# audio.net
KiCad netlist of a schematic drawn in Altium Designer
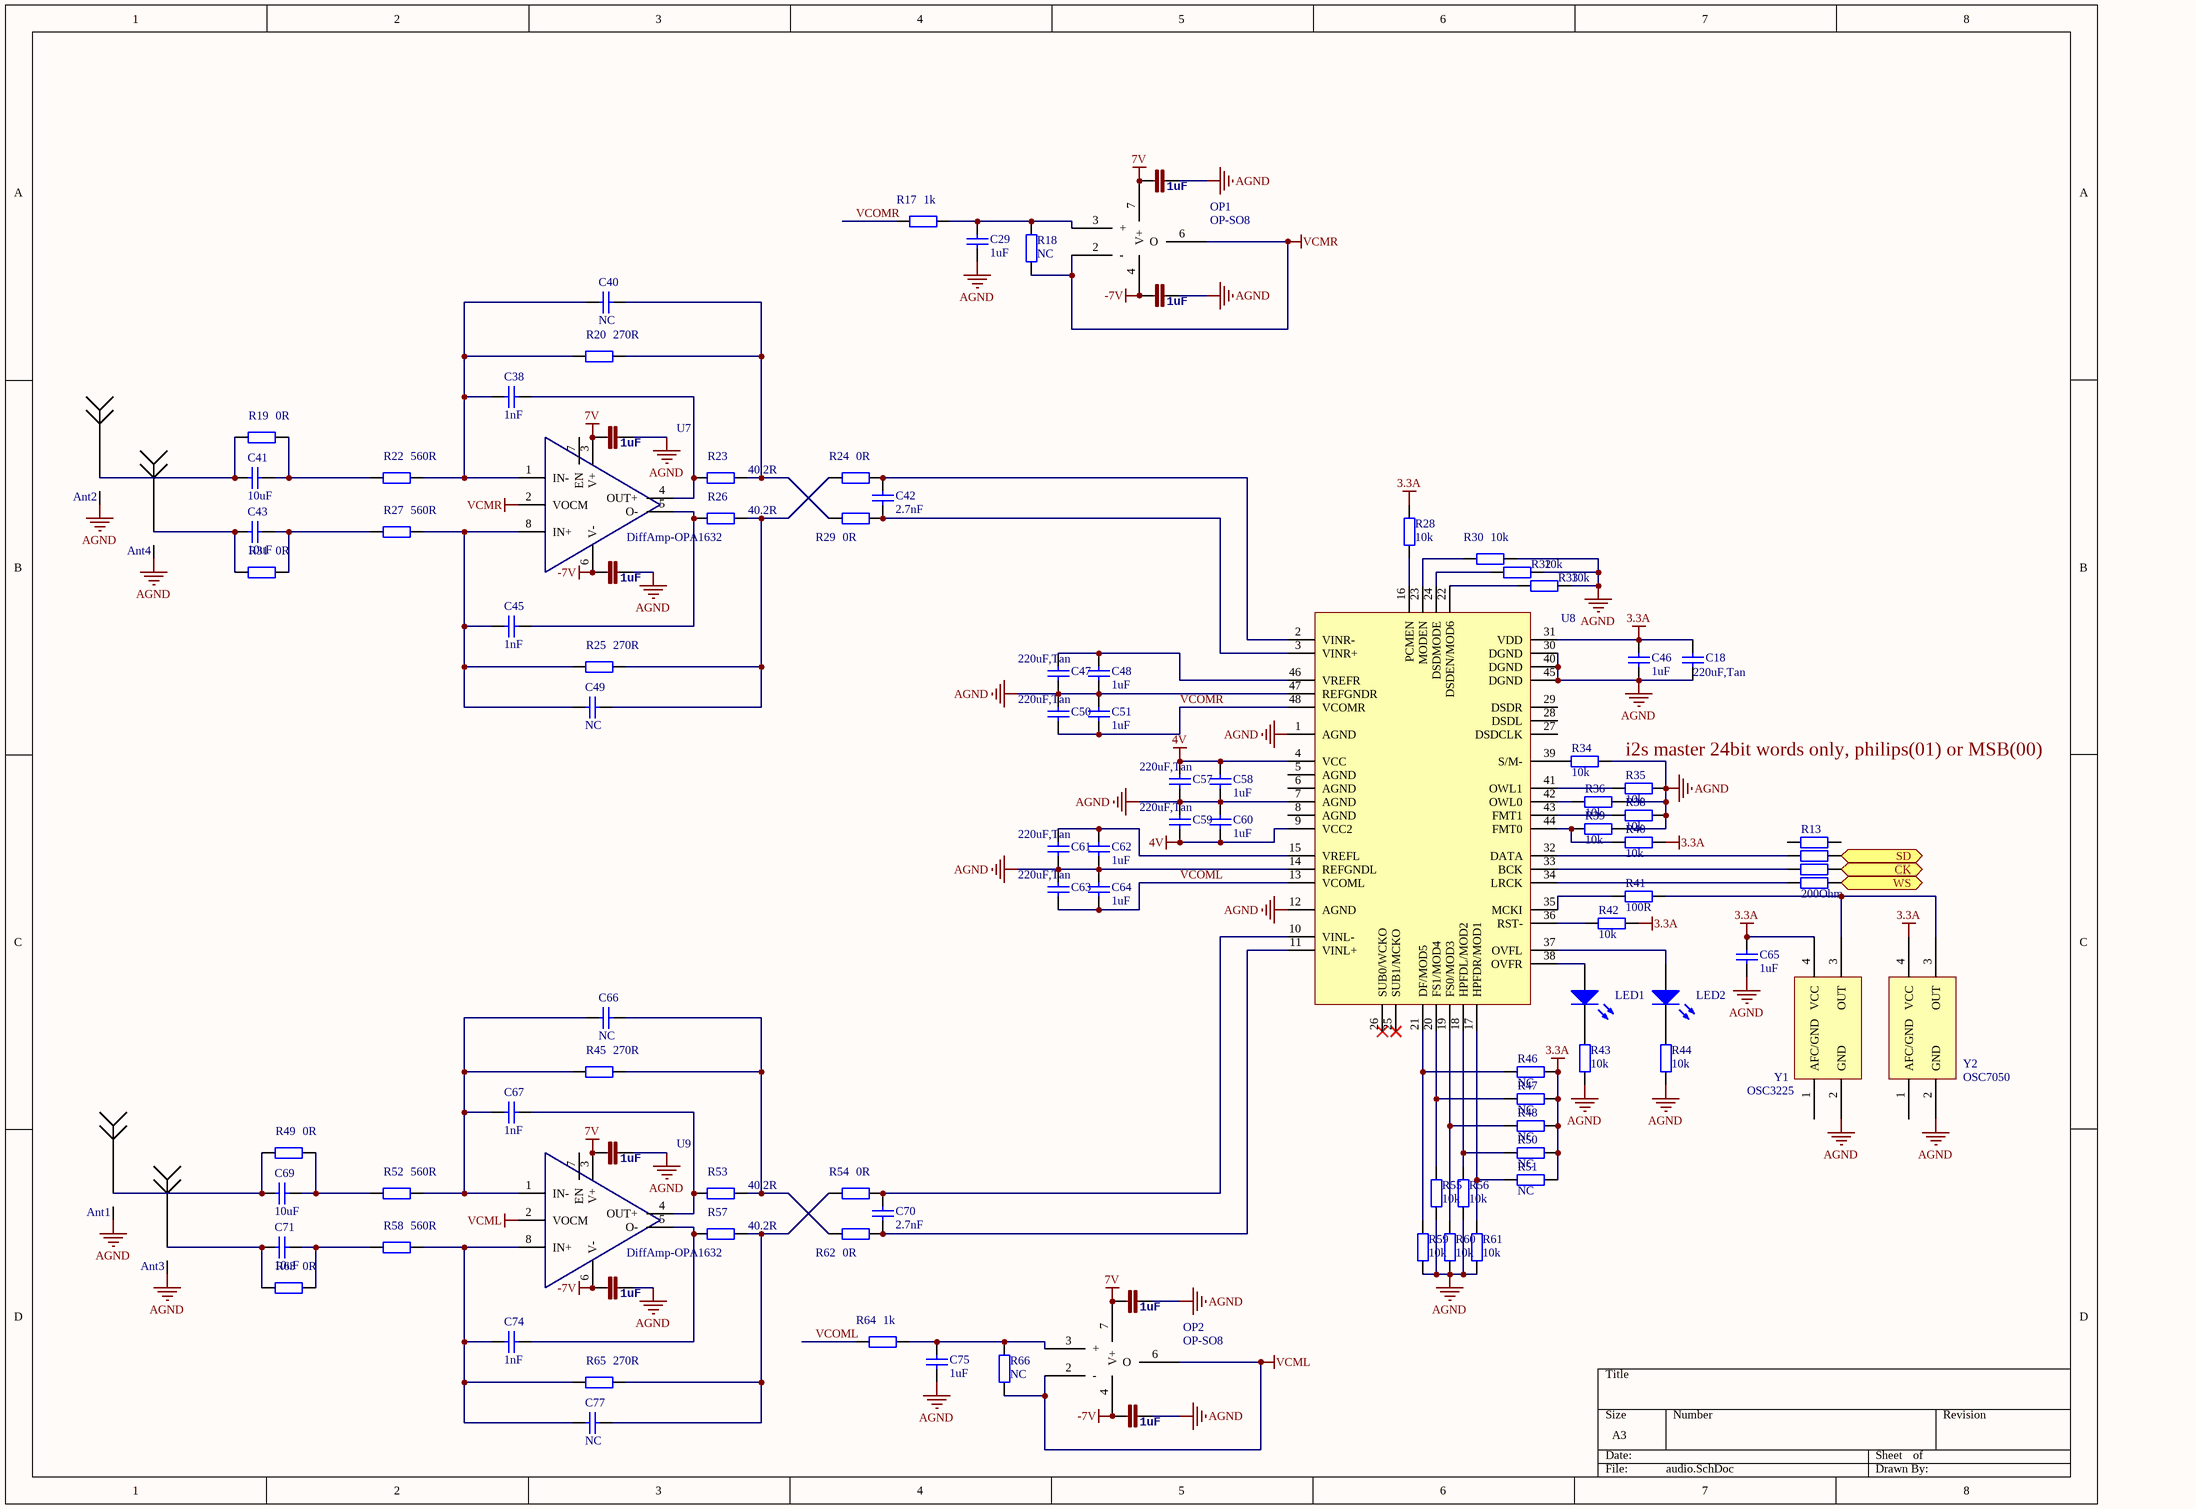
[diagram p0: audio.SchDoc]

(export (version "E")
  (design (tool "Eeschema 10.0.6"))
  (components
    (comp (ref "Ant1") (value "Antenna") (footprint "SMA-2C") (libsource (lib "F4SDR") (part "Antenna")))
    (comp (ref "Ant2")
      (value "Antenna")
      (footprint "BK5811:SMA-2C")
      (libsource (lib "F4SDR") (part "Antenna"))
    )
    (comp (ref "Ant3") (value "Antenna") (footprint "SMA-2C") (libsource (lib "F4SDR") (part "Antenna")))
    (comp (ref "Ant4") (value "Antenna") (footprint "SMA-2C") (libsource (lib "F4SDR") (part "Antenna")))
    (comp (ref "C18")
      (value "220uF,Tan")
      (footprint "1210")
      (description "Capacitor")
      (fields (field (name "PUBLISHER") "Altium Limited"))
      (libsource (lib "RTC6705") (part "Cap"))
    )
    (comp (ref "C29")
      (value "1uF")
      (footprint "0402")
      (description "Capacitor")
      (libsource (lib "RTC6705") (part "Cap"))
    )
    (comp (ref "C37")
      (value "1uF")
      (footprint "0603L")
      (description "<b>Capacitor</b>\nStandard 0603 ceramic capacitor, and 0.1\" leaded capacitor.")
      (fields (field (name "PARTNO") "CC0402ZRY5V7BB104"))
      (libsource (lib "pixhawk2") (part "CAP0402-CAP"))
    )
    (comp (ref "C38")
      (value "1nF")
      (footprint "0805")
      (description "Capacitor")
      (fields (field (name "PUBLISHER") "Altium Limited"))
      (libsource (lib "RTC6705") (part "Cap"))
    )
    (comp (ref "C39")
      (value "1uF")
      (footprint "0603L")
      (description "<b>Capacitor</b>\nStandard 0603 ceramic capacitor, and 0.1\" leaded capacitor.")
      (fields (field (name "PARTNO") "CC0402ZRY5V7BB104"))
      (libsource (lib "pixhawk2") (part "CAP0402-CAP"))
    )
    (comp (ref "C40")
      (value "NC")
      (footprint "0805")
      (description "Capacitor")
      (fields (field (name "PUBLISHER") "Altium Limited"))
      (libsource (lib "RTC6705") (part "Cap"))
    )
    (comp (ref "C41")
      (value "10uF")
      (footprint "CL21-5mm-1F")
      (description "Capacitor")
      (fields (field (name "PUBLISHER") "Altium Limited"))
      (libsource (lib "RTC6705") (part "Cap"))
    )
    (comp (ref "C42")
      (value "2.7nF")
      (footprint "0805")
      (description "Capacitor")
      (fields (field (name "PUBLISHER") "Altium Limited"))
      (libsource (lib "RTC6705") (part "Cap"))
    )
    (comp (ref "C43")
      (value "10uF")
      (footprint "CL21-5mm-1F")
      (description "Capacitor")
      (fields (field (name "PUBLISHER") "Altium Limited"))
      (libsource (lib "RTC6705") (part "Cap"))
    )
    (comp (ref "C44")
      (value "1uF")
      (footprint "0603L")
      (description "<b>Capacitor</b>\nStandard 0603 ceramic capacitor, and 0.1\" leaded capacitor.")
      (fields (field (name "PARTNO") "CC0402ZRY5V7BB104"))
      (libsource (lib "pixhawk2") (part "CAP0402-CAP"))
    )
    (comp (ref "C45")
      (value "1nF")
      (footprint "0805")
      (description "Capacitor")
      (fields (field (name "PUBLISHER") "Altium Limited"))
      (libsource (lib "RTC6705") (part "Cap"))
    )
    (comp (ref "C46")
      (value "1uF")
      (footprint "0402")
      (description "Capacitor")
      (libsource (lib "RTC6705") (part "Cap"))
    )
    (comp (ref "C47")
      (value "220uF,Tan")
      (footprint "1210")
      (description "Capacitor")
      (fields (field (name "PUBLISHER") "Altium Limited"))
      (libsource (lib "RTC6705") (part "Cap"))
    )
    (comp (ref "C48")
      (value "1uF")
      (footprint "0402")
      (description "Capacitor")
      (libsource (lib "RTC6705") (part "Cap"))
    )
    (comp (ref "C49")
      (value "NC")
      (footprint "0805")
      (description "Capacitor")
      (fields (field (name "PUBLISHER") "Altium Limited"))
      (libsource (lib "RTC6705") (part "Cap"))
    )
    (comp (ref "C50")
      (value "220uF,Tan")
      (footprint "1210")
      (description "Capacitor")
      (fields (field (name "PUBLISHER") "Altium Limited"))
      (libsource (lib "RTC6705") (part "Cap"))
    )
    (comp (ref "C51")
      (value "1uF")
      (footprint "0402")
      (description "Capacitor")
      (libsource (lib "RTC6705") (part "Cap"))
    )
    (comp (ref "C57")
      (value "220uF,Tan")
      (footprint "1210")
      (description "Capacitor")
      (fields (field (name "PUBLISHER") "Altium Limited"))
      (libsource (lib "RTC6705") (part "Cap"))
    )
    (comp (ref "C58")
      (value "1uF")
      (footprint "0402")
      (description "Capacitor")
      (libsource (lib "RTC6705") (part "Cap"))
    )
    (comp (ref "C59")
      (value "220uF,Tan")
      (footprint "1210")
      (description "Capacitor")
      (fields (field (name "PUBLISHER") "Altium Limited"))
      (libsource (lib "RTC6705") (part "Cap"))
    )
    (comp (ref "C60")
      (value "1uF")
      (footprint "0402")
      (description "Capacitor")
      (libsource (lib "RTC6705") (part "Cap"))
    )
    (comp (ref "C61")
      (value "220uF,Tan")
      (footprint "1210")
      (description "Capacitor")
      (fields (field (name "PUBLISHER") "Altium Limited"))
      (libsource (lib "RTC6705") (part "Cap"))
    )
    (comp (ref "C62")
      (value "1uF")
      (footprint "0402")
      (description "Capacitor")
      (libsource (lib "RTC6705") (part "Cap"))
    )
    (comp (ref "C63")
      (value "220uF,Tan")
      (footprint "1210")
      (description "Capacitor")
      (fields (field (name "PUBLISHER") "Altium Limited"))
      (libsource (lib "RTC6705") (part "Cap"))
    )
    (comp (ref "C64")
      (value "1uF")
      (footprint "0402")
      (description "Capacitor")
      (libsource (lib "RTC6705") (part "Cap"))
    )
    (comp (ref "C65")
      (value "1uF")
      (footprint "0402")
      (description "Capacitor")
      (libsource (lib "RTC6705") (part "Cap"))
    )
    (comp (ref "C66")
      (value "NC")
      (footprint "0805")
      (description "Capacitor")
      (fields (field (name "PUBLISHER") "Altium Limited"))
      (libsource (lib "RTC6705") (part "Cap"))
    )
    (comp (ref "C67")
      (value "1nF")
      (footprint "0805")
      (description "Capacitor")
      (fields (field (name "PUBLISHER") "Altium Limited"))
      (libsource (lib "RTC6705") (part "Cap"))
    )
    (comp (ref "C68")
      (value "1uF")
      (footprint "0603L")
      (description "<b>Capacitor</b>\nStandard 0603 ceramic capacitor, and 0.1\" leaded capacitor.")
      (fields (field (name "PARTNO") "CC0402ZRY5V7BB104"))
      (libsource (lib "pixhawk2") (part "CAP0402-CAP"))
    )
    (comp (ref "C69")
      (value "10uF")
      (footprint "CL21-5mm-1F")
      (description "Capacitor")
      (fields (field (name "PUBLISHER") "Altium Limited"))
      (libsource (lib "RTC6705") (part "Cap"))
    )
    (comp (ref "C70")
      (value "2.7nF")
      (footprint "0805")
      (description "Capacitor")
      (fields (field (name "PUBLISHER") "Altium Limited"))
      (libsource (lib "RTC6705") (part "Cap"))
    )
    (comp (ref "C71")
      (value "10uF")
      (footprint "CL21-5mm-1F")
      (description "Capacitor")
      (fields (field (name "PUBLISHER") "Altium Limited"))
      (libsource (lib "RTC6705") (part "Cap"))
    )
    (comp (ref "C72")
      (value "1uF")
      (footprint "0603L")
      (description "<b>Capacitor</b>\nStandard 0603 ceramic capacitor, and 0.1\" leaded capacitor.")
      (fields (field (name "PARTNO") "CC0402ZRY5V7BB104"))
      (libsource (lib "pixhawk2") (part "CAP0402-CAP"))
    )
    (comp (ref "C73")
      (value "1uF")
      (footprint "0603L")
      (description "<b>Capacitor</b>\nStandard 0603 ceramic capacitor, and 0.1\" leaded capacitor.")
      (fields (field (name "PARTNO") "CC0402ZRY5V7BB104"))
      (libsource (lib "pixhawk2") (part "CAP0402-CAP"))
    )
    (comp (ref "C74")
      (value "1nF")
      (footprint "0805")
      (description "Capacitor")
      (fields (field (name "PUBLISHER") "Altium Limited"))
      (libsource (lib "RTC6705") (part "Cap"))
    )
    (comp (ref "C75")
      (value "1uF")
      (footprint "0402")
      (description "Capacitor")
      (libsource (lib "RTC6705") (part "Cap"))
    )
    (comp (ref "C76")
      (value "1uF")
      (footprint "0603L")
      (description "<b>Capacitor</b>\nStandard 0603 ceramic capacitor, and 0.1\" leaded capacitor.")
      (fields (field (name "PARTNO") "CC0402ZRY5V7BB104"))
      (libsource (lib "pixhawk2") (part "CAP0402-CAP"))
    )
    (comp (ref "C77")
      (value "NC")
      (footprint "0805")
      (description "Capacitor")
      (fields (field (name "PUBLISHER") "Altium Limited"))
      (libsource (lib "RTC6705") (part "Cap"))
    )
    (comp (ref "C89")
      (value "1uF")
      (footprint "0603L")
      (description "<b>Capacitor</b>\nStandard 0603 ceramic capacitor, and 0.1\" leaded capacitor.")
      (fields (field (name "PARTNO") "CC0402ZRY5V7BB104"))
      (libsource (lib "pixhawk2") (part "CAP0402-CAP"))
    )
    (comp (ref "LED1")
      (value "LED0")
      (footprint "0603")
      (description "Typical INFRARED GaAs LED")
      (fields (field (name "PUBLISHER") "Altium Limited"))
      (libsource (lib "Miscellaneous Devices") (part "LED0"))
    )
    (comp (ref "LED2")
      (value "LED0")
      (footprint "0603")
      (description "Typical INFRARED GaAs LED")
      (fields (field (name "PUBLISHER") "Altium Limited"))
      (libsource (lib "Miscellaneous Devices") (part "LED0"))
    )
    (comp (ref "OP1") (value "OP-SO8") (footprint "D8") (libsource (lib "sch") (part "OP-SO8")))
    (comp (ref "OP2") (value "OP-SO8") (footprint "D8") (libsource (lib "sch") (part "OP-SO8")))
    (comp (ref "R13")
      (value "200Ohm")
      (footprint "0402X4")
      (description "Resistor")
      (fields (field (name "Comment") "Res*4") (field (name "PUBLISHER") "Altium Limited"))
      (libsource (lib "sch") (part "Res*4"))
    )
    (comp (ref "R17")
      (value "1k")
      (footprint "0402")
      (description "Resistor")
      (fields (field (name "PUBLISHER") "Altium Limited"))
      (libsource (lib "Miscellaneous Devices") (part "Res2"))
    )
    (comp (ref "R18")
      (value "NC")
      (footprint "0402")
      (description "Resistor")
      (fields (field (name "PUBLISHER") "Altium Limited"))
      (libsource (lib "") (part "Res2_3"))
    )
    (comp (ref "R19")
      (value "0R")
      (footprint "0402")
      (description "Resistor")
      (fields (field (name "PUBLISHER") "Altium Limited"))
      (libsource (lib "Miscellaneous Devices") (part "Res2"))
    )
    (comp (ref "R20")
      (value "270R")
      (footprint "0402")
      (description "Resistor")
      (fields (field (name "PUBLISHER") "Altium Limited"))
      (libsource (lib "Miscellaneous Devices") (part "Res2"))
    )
    (comp (ref "R22")
      (value "560R")
      (footprint "0402")
      (description "Resistor")
      (fields (field (name "PUBLISHER") "Altium Limited"))
      (libsource (lib "Miscellaneous Devices") (part "Res2"))
    )
    (comp (ref "R23")
      (value "40.2R")
      (footprint "0805")
      (description "Resistor")
      (fields (field (name "PUBLISHER") "Altium Limited"))
      (libsource (lib "Miscellaneous Devices") (part "Res2"))
    )
    (comp (ref "R24")
      (value "0R")
      (footprint "0402")
      (description "Resistor")
      (fields (field (name "PUBLISHER") "Altium Limited"))
      (libsource (lib "Miscellaneous Devices") (part "Res2"))
    )
    (comp (ref "R25")
      (value "270R")
      (footprint "0402")
      (description "Resistor")
      (fields (field (name "PUBLISHER") "Altium Limited"))
      (libsource (lib "Miscellaneous Devices") (part "Res2"))
    )
    (comp (ref "R26")
      (value "40.2R")
      (footprint "0805")
      (description "Resistor")
      (fields (field (name "PUBLISHER") "Altium Limited"))
      (libsource (lib "Miscellaneous Devices") (part "Res2"))
    )
    (comp (ref "R27")
      (value "560R")
      (footprint "0402")
      (description "Resistor")
      (fields (field (name "PUBLISHER") "Altium Limited"))
      (libsource (lib "Miscellaneous Devices") (part "Res2"))
    )
    (comp (ref "R28")
      (value "10k")
      (footprint "0402")
      (description "Resistor")
      (fields (field (name "PUBLISHER") "Altium Limited"))
      (libsource (lib "") (part "Res2_3"))
    )
    (comp (ref "R29")
      (value "0R")
      (footprint "0402")
      (description "Resistor")
      (fields (field (name "PUBLISHER") "Altium Limited"))
      (libsource (lib "Miscellaneous Devices") (part "Res2"))
    )
    (comp (ref "R30")
      (value "10k")
      (footprint "0402")
      (description "Resistor")
      (fields (field (name "PUBLISHER") "Altium Limited"))
      (libsource (lib "Miscellaneous Devices") (part "Res2"))
    )
    (comp (ref "R31")
      (value "0R")
      (footprint "0402")
      (description "Resistor")
      (fields (field (name "PUBLISHER") "Altium Limited"))
      (libsource (lib "Miscellaneous Devices") (part "Res2"))
    )
    (comp (ref "R32")
      (value "10k")
      (footprint "0402")
      (description "Resistor")
      (fields (field (name "PUBLISHER") "Altium Limited"))
      (libsource (lib "Miscellaneous Devices") (part "Res2"))
    )
    (comp (ref "R33")
      (value "10k")
      (footprint "0402")
      (description "Resistor")
      (fields (field (name "PUBLISHER") "Altium Limited"))
      (libsource (lib "Miscellaneous Devices") (part "Res2"))
    )
    (comp (ref "R34")
      (value "10k")
      (footprint "0402")
      (description "Resistor")
      (fields (field (name "PUBLISHER") "Altium Limited"))
      (libsource (lib "") (part "Res2_1"))
    )
    (comp (ref "R35")
      (value "10k")
      (footprint "0402")
      (description "Resistor")
      (fields (field (name "PUBLISHER") "Altium Limited"))
      (libsource (lib "") (part "Res2_1"))
    )
    (comp (ref "R36")
      (value "10k")
      (footprint "0402")
      (description "Resistor")
      (fields (field (name "PUBLISHER") "Altium Limited"))
      (libsource (lib "") (part "Res2_1"))
    )
    (comp (ref "R38")
      (value "10k")
      (footprint "0402")
      (description "Resistor")
      (fields (field (name "PUBLISHER") "Altium Limited"))
      (libsource (lib "") (part "Res2_1"))
    )
    (comp (ref "R39")
      (value "10k")
      (footprint "0402")
      (description "Resistor")
      (fields (field (name "PUBLISHER") "Altium Limited"))
      (libsource (lib "") (part "Res2_1"))
    )
    (comp (ref "R40")
      (value "10k")
      (footprint "0402")
      (description "Resistor")
      (fields (field (name "PUBLISHER") "Altium Limited"))
      (libsource (lib "") (part "Res2_1"))
    )
    (comp (ref "R41")
      (value "100R")
      (footprint "0402")
      (description "Resistor")
      (fields (field (name "PUBLISHER") "Altium Limited"))
      (libsource (lib "") (part "Res2_1"))
    )
    (comp (ref "R42")
      (value "10k")
      (footprint "0402")
      (description "Resistor")
      (fields (field (name "PUBLISHER") "Altium Limited"))
      (libsource (lib "") (part "Res2_1"))
    )
    (comp (ref "R43")
      (value "10k")
      (footprint "0402")
      (description "Resistor")
      (fields (field (name "PUBLISHER") "Altium Limited"))
      (libsource (lib "") (part "Res2_3"))
    )
    (comp (ref "R44")
      (value "10k")
      (footprint "0402")
      (description "Resistor")
      (fields (field (name "PUBLISHER") "Altium Limited"))
      (libsource (lib "") (part "Res2_3"))
    )
    (comp (ref "R45")
      (value "270R")
      (footprint "0402")
      (description "Resistor")
      (fields (field (name "PUBLISHER") "Altium Limited"))
      (libsource (lib "Miscellaneous Devices") (part "Res2"))
    )
    (comp (ref "R46")
      (value "NC")
      (footprint "0402")
      (description "Resistor")
      (fields (field (name "PUBLISHER") "Altium Limited"))
      (libsource (lib "Miscellaneous Devices") (part "Res2"))
    )
    (comp (ref "R47")
      (value "NC")
      (footprint "0402")
      (description "Resistor")
      (fields (field (name "PUBLISHER") "Altium Limited"))
      (libsource (lib "") (part "Res2_1"))
    )
    (comp (ref "R48")
      (value "NC")
      (footprint "0402")
      (description "Resistor")
      (fields (field (name "PUBLISHER") "Altium Limited"))
      (libsource (lib "") (part "Res2_1"))
    )
    (comp (ref "R49")
      (value "0R")
      (footprint "0402")
      (description "Resistor")
      (fields (field (name "PUBLISHER") "Altium Limited"))
      (libsource (lib "Miscellaneous Devices") (part "Res2"))
    )
    (comp (ref "R50")
      (value "NC")
      (footprint "0402")
      (description "Resistor")
      (fields (field (name "PUBLISHER") "Altium Limited"))
      (libsource (lib "") (part "Res2_1"))
    )
    (comp (ref "R51")
      (value "NC")
      (footprint "0402")
      (description "Resistor")
      (fields (field (name "PUBLISHER") "Altium Limited"))
      (libsource (lib "Miscellaneous Devices") (part "Res2"))
    )
    (comp (ref "R52")
      (value "560R")
      (footprint "0402")
      (description "Resistor")
      (fields (field (name "PUBLISHER") "Altium Limited"))
      (libsource (lib "Miscellaneous Devices") (part "Res2"))
    )
    (comp (ref "R53")
      (value "40.2R")
      (footprint "0805")
      (description "Resistor")
      (fields (field (name "PUBLISHER") "Altium Limited"))
      (libsource (lib "Miscellaneous Devices") (part "Res2"))
    )
    (comp (ref "R54")
      (value "0R")
      (footprint "0402")
      (description "Resistor")
      (fields (field (name "PUBLISHER") "Altium Limited"))
      (libsource (lib "Miscellaneous Devices") (part "Res2"))
    )
    (comp (ref "R55")
      (value "10k")
      (footprint "0402")
      (description "Resistor")
      (fields (field (name "PUBLISHER") "Altium Limited"))
      (libsource (lib "") (part "Res2_2"))
    )
    (comp (ref "R56")
      (value "10k")
      (footprint "0402")
      (description "Resistor")
      (fields (field (name "PUBLISHER") "Altium Limited"))
      (libsource (lib "") (part "Res2_2"))
    )
    (comp (ref "R57")
      (value "40.2R")
      (footprint "0805")
      (description "Resistor")
      (fields (field (name "PUBLISHER") "Altium Limited"))
      (libsource (lib "Miscellaneous Devices") (part "Res2"))
    )
    (comp (ref "R58")
      (value "560R")
      (footprint "0402")
      (description "Resistor")
      (fields (field (name "PUBLISHER") "Altium Limited"))
      (libsource (lib "Miscellaneous Devices") (part "Res2"))
    )
    (comp (ref "R59")
      (value "10k")
      (footprint "0402")
      (description "Resistor")
      (fields (field (name "PUBLISHER") "Altium Limited"))
      (libsource (lib "") (part "Res2_2"))
    )
    (comp (ref "R60")
      (value "10k")
      (footprint "0402")
      (description "Resistor")
      (fields (field (name "PUBLISHER") "Altium Limited"))
      (libsource (lib "") (part "Res2_2"))
    )
    (comp (ref "R61")
      (value "10k")
      (footprint "0402")
      (description "Resistor")
      (fields (field (name "PUBLISHER") "Altium Limited"))
      (libsource (lib "") (part "Res2_2"))
    )
    (comp (ref "R62")
      (value "0R")
      (footprint "0402")
      (description "Resistor")
      (fields (field (name "PUBLISHER") "Altium Limited"))
      (libsource (lib "Miscellaneous Devices") (part "Res2"))
    )
    (comp (ref "R63")
      (value "0R")
      (footprint "0402")
      (description "Resistor")
      (fields (field (name "PUBLISHER") "Altium Limited"))
      (libsource (lib "Miscellaneous Devices") (part "Res2"))
    )
    (comp (ref "R64")
      (value "1k")
      (footprint "0402")
      (description "Resistor")
      (fields (field (name "PUBLISHER") "Altium Limited"))
      (libsource (lib "Miscellaneous Devices") (part "Res2"))
    )
    (comp (ref "R65")
      (value "270R")
      (footprint "0402")
      (description "Resistor")
      (fields (field (name "PUBLISHER") "Altium Limited"))
      (libsource (lib "Miscellaneous Devices") (part "Res2"))
    )
    (comp (ref "R66")
      (value "NC")
      (footprint "0402")
      (description "Resistor")
      (fields (field (name "PUBLISHER") "Altium Limited"))
      (libsource (lib "") (part "Res2_3"))
    )
    (comp (ref "U7")
      (value "DiffAmp-OPA1632")
      (footprint "MSOP8/VSSOP8")
      (libsource (lib "F4SDR") (part "DiffAmp"))
    )
    (comp (ref "U8")
      (value "PCM4222-FUNC")
      (footprint "PCM4222")
      (libsource (lib "ADAU1761") (part "PCM4222-FUNC"))
    )
    (comp (ref "U9")
      (value "DiffAmp-OPA1632")
      (footprint "MSOP8/VSSOP8")
      (libsource (lib "F4SDR") (part "DiffAmp"))
    )
    (comp (ref "Y1") (value "OSC3225") (footprint "TXC_7Q") (libsource (lib "F4SDR") (part "OSC_40M")))
    (comp (ref "Y2") (value "OSC7050") (footprint "OSC7050") (libsource (lib "F4SDR") (part "OSC_40M")))
  )
  (nets
    (net (code "1") (name "-7V") (class "Default")
      (node (ref "C37") (pin "2") (pinfunction "2_2") (pintype "passive"))
      (node (ref "C44") (pin "2") (pinfunction "2_2") (pintype "passive"))
      (node (ref "C72") (pin "2") (pinfunction "2_2") (pintype "passive"))
      (node (ref "C76") (pin "2") (pinfunction "2_2") (pintype "passive"))
      (node (ref "OP1") (pin "4") (pinfunction "5_4") (pintype "passive"))
      (node (ref "OP2") (pin "4") (pinfunction "5_4") (pintype "passive"))
      (node (ref "U7") (pin "6") (pinfunction "V-_6") (pintype "passive"))
      (node (ref "U9") (pin "6") (pinfunction "V-_6") (pintype "passive"))
    )
    (net (code "2") (name "/CK") (class "Default")
      (node (ref "R13") (pin "7") (pinfunction "7_7") (pintype "passive"))
    )
    (net (code "3") (name "/SD") (class "Default")
      (node (ref "R13") (pin "6") (pinfunction "6_6") (pintype "passive"))
    )
    (net (code "4") (name "/VCOML") (class "Default")
      (node (ref "C63") (pin "2") (pinfunction "2_2") (pintype "passive"))
      (node (ref "C64") (pin "1") (pinfunction "1_1") (pintype "passive"))
      (node (ref "R64") (pin "2") (pinfunction "2_2") (pintype "passive"))
      (node (ref "U8") (pin "13") (pinfunction "VCOML_13") (pintype "passive"))
    )
    (net (code "5") (name "/VCOMR") (class "Default")
      (node (ref "C50") (pin "2") (pinfunction "2_2") (pintype "passive"))
      (node (ref "C51") (pin "1") (pinfunction "1_1") (pintype "passive"))
      (node (ref "R17") (pin "2") (pinfunction "2_2") (pintype "passive"))
      (node (ref "U8") (pin "48") (pinfunction "VCOMR_48") (pintype "passive"))
    )
    (net (code "6") (name "/WS") (class "Default")
      (node (ref "R13") (pin "8") (pinfunction "8_8") (pintype "passive"))
    )
    (net (code "7") (name "3.3A") (class "Default")
      (node (ref "C18") (pin "2") (pinfunction "2_2") (pintype "passive"))
      (node (ref "C46") (pin "2") (pinfunction "2_2") (pintype "passive"))
      (node (ref "C65") (pin "2") (pinfunction "2_2") (pintype "passive"))
      (node (ref "R28") (pin "1") (pinfunction "1_1") (pintype "passive"))
      (node (ref "R40") (pin "2") (pinfunction "2_2") (pintype "passive"))
      (node (ref "R42") (pin "2") (pinfunction "2_2") (pintype "passive"))
      (node (ref "R46") (pin "1") (pinfunction "1_1") (pintype "passive"))
      (node (ref "R47") (pin "2") (pinfunction "2_2") (pintype "passive"))
      (node (ref "R48") (pin "2") (pinfunction "2_2") (pintype "passive"))
      (node (ref "R50") (pin "2") (pinfunction "2_2") (pintype "passive"))
      (node (ref "R51") (pin "1") (pinfunction "1_1") (pintype "passive"))
      (node (ref "U8") (pin "31") (pinfunction "VDD_31") (pintype "passive"))
      (node (ref "Y1") (pin "4") (pinfunction "VCC_4") (pintype "passive"))
      (node (ref "Y2") (pin "4") (pinfunction "VCC_4") (pintype "passive"))
    )
    (net (code "8") (name "4V") (class "Default")
      (node (ref "C57") (pin "1") (pinfunction "1_1") (pintype "passive"))
      (node (ref "C58") (pin "2") (pinfunction "2_2") (pintype "passive"))
      (node (ref "C59") (pin "2") (pinfunction "2_2") (pintype "passive"))
      (node (ref "C60") (pin "1") (pinfunction "1_1") (pintype "passive"))
      (node (ref "U8") (pin "4") (pinfunction "VCC_4") (pintype "passive"))
      (node (ref "U8") (pin "9") (pinfunction "VCC2_9") (pintype "passive"))
    )
    (net (code "9") (name "7V") (class "Default")
      (node (ref "C39") (pin "2") (pinfunction "2_2") (pintype "passive"))
      (node (ref "C68") (pin "2") (pinfunction "2_2") (pintype "passive"))
      (node (ref "C73") (pin "2") (pinfunction "2_2") (pintype "passive"))
      (node (ref "C89") (pin "2") (pinfunction "2_2") (pintype "passive"))
      (node (ref "OP1") (pin "7") (pinfunction "V+_7") (pintype "passive"))
      (node (ref "OP2") (pin "7") (pinfunction "V+_7") (pintype "passive"))
      (node (ref "U7") (pin "3") (pinfunction "V+_3") (pintype "passive"))
      (node (ref "U9") (pin "3") (pinfunction "V+_3") (pintype "passive"))
    )
    (net (code "10") (name "AGND") (class "Default")
      (node (ref "Ant1") (pin "GND") (pinfunction "G_GND") (pintype "passive"))
      (node (ref "Ant2") (pin "GND") (pinfunction "G_GND") (pintype "passive"))
      (node (ref "Ant3") (pin "GND") (pinfunction "G_GND") (pintype "passive"))
      (node (ref "Ant4") (pin "GND") (pinfunction "G_GND") (pintype "passive"))
      (node (ref "C18") (pin "1") (pinfunction "1_1") (pintype "passive"))
      (node (ref "C29") (pin "1") (pinfunction "1_1") (pintype "passive"))
      (node (ref "C37") (pin "1") (pinfunction "1_1") (pintype "passive"))
      (node (ref "C39") (pin "1") (pinfunction "1_1") (pintype "passive"))
      (node (ref "C44") (pin "1") (pinfunction "1_1") (pintype "passive"))
      (node (ref "C46") (pin "1") (pinfunction "1_1") (pintype "passive"))
      (node (ref "C47") (pin "2") (pinfunction "2_2") (pintype "passive"))
      (node (ref "C48") (pin "1") (pinfunction "1_1") (pintype "passive"))
      (node (ref "C50") (pin "1") (pinfunction "1_1") (pintype "passive"))
      (node (ref "C51") (pin "2") (pinfunction "2_2") (pintype "passive"))
      (node (ref "C57") (pin "2") (pinfunction "2_2") (pintype "passive"))
      (node (ref "C58") (pin "1") (pinfunction "1_1") (pintype "passive"))
      (node (ref "C59") (pin "1") (pinfunction "1_1") (pintype "passive"))
      (node (ref "C60") (pin "2") (pinfunction "2_2") (pintype "passive"))
      (node (ref "C61") (pin "2") (pinfunction "2_2") (pintype "passive"))
      (node (ref "C62") (pin "1") (pinfunction "1_1") (pintype "passive"))
      (node (ref "C63") (pin "1") (pinfunction "1_1") (pintype "passive"))
      (node (ref "C64") (pin "2") (pinfunction "2_2") (pintype "passive"))
      (node (ref "C65") (pin "1") (pinfunction "1_1") (pintype "passive"))
      (node (ref "C68") (pin "1") (pinfunction "1_1") (pintype "passive"))
      (node (ref "C72") (pin "1") (pinfunction "1_1") (pintype "passive"))
      (node (ref "C73") (pin "1") (pinfunction "1_1") (pintype "passive"))
      (node (ref "C75") (pin "1") (pinfunction "1_1") (pintype "passive"))
      (node (ref "C76") (pin "1") (pinfunction "1_1") (pintype "passive"))
      (node (ref "C89") (pin "1") (pinfunction "1_1") (pintype "passive"))
      (node (ref "R30") (pin "1") (pinfunction "1_1") (pintype "passive"))
      (node (ref "R32") (pin "1") (pinfunction "1_1") (pintype "passive"))
      (node (ref "R33") (pin "1") (pinfunction "1_1") (pintype "passive"))
      (node (ref "R34") (pin "2") (pinfunction "2_2") (pintype "passive"))
      (node (ref "R35") (pin "2") (pinfunction "2_2") (pintype "passive"))
      (node (ref "R36") (pin "2") (pinfunction "2_2") (pintype "passive"))
      (node (ref "R38") (pin "2") (pinfunction "2_2") (pintype "passive"))
      (node (ref "R39") (pin "2") (pinfunction "2_2") (pintype "passive"))
      (node (ref "R43") (pin "2") (pinfunction "2_2") (pintype "passive"))
      (node (ref "R44") (pin "2") (pinfunction "2_2") (pintype "passive"))
      (node (ref "R55") (pin "1") (pinfunction "1_1") (pintype "passive"))
      (node (ref "R56") (pin "1") (pinfunction "1_1") (pintype "passive"))
      (node (ref "R59") (pin "1") (pinfunction "1_1") (pintype "passive"))
      (node (ref "R60") (pin "1") (pinfunction "1_1") (pintype "passive"))
      (node (ref "R61") (pin "1") (pinfunction "1_1") (pintype "passive"))
      (node (ref "U8") (pin "1") (pinfunction "AGND_1") (pintype "passive"))
      (node (ref "U8") (pin "12") (pinfunction "AGND_12") (pintype "passive"))
      (node (ref "U8") (pin "14") (pinfunction "REFGNDL_14") (pintype "passive"))
      (node (ref "U8") (pin "30") (pinfunction "DGND_30") (pintype "passive"))
      (node (ref "U8") (pin "40") (pinfunction "DGND_40") (pintype "passive"))
      (node (ref "U8") (pin "45") (pinfunction "DGND_45") (pintype "passive"))
      (node (ref "U8") (pin "47") (pinfunction "REFGNDR_47") (pintype "passive"))
      (node (ref "U8") (pin "7") (pinfunction "AGND_7") (pintype "passive"))
      (node (ref "Y1") (pin "2") (pinfunction "GND_2") (pintype "passive"))
      (node (ref "Y2") (pin "2") (pinfunction "GND_2") (pintype "passive"))
    )
    (net (code "11") (name "Net-(Ant1-Pad1)") (class "Default")
      (node (ref "Ant1") (pin "1") (pinfunction "1_1") (pintype "passive"))
      (node (ref "C69") (pin "2") (pinfunction "2_2") (pintype "passive"))
      (node (ref "R49") (pin "2") (pinfunction "2_2") (pintype "passive"))
    )
    (net (code "12") (name "Net-(Ant2-Pad1)") (class "Default")
      (node (ref "Ant2") (pin "1") (pinfunction "1_1") (pintype "passive"))
      (node (ref "C41") (pin "2") (pinfunction "2_2") (pintype "passive"))
      (node (ref "R19") (pin "2") (pinfunction "2_2") (pintype "passive"))
    )
    (net (code "13") (name "Net-(Ant3-Pad1)") (class "Default")
      (node (ref "Ant3") (pin "1") (pinfunction "1_1") (pintype "passive"))
      (node (ref "C71") (pin "2") (pinfunction "2_2") (pintype "passive"))
      (node (ref "R63") (pin "2") (pinfunction "2_2") (pintype "passive"))
    )
    (net (code "14") (name "Net-(Ant4-Pad1)") (class "Default")
      (node (ref "Ant4") (pin "1") (pinfunction "1_1") (pintype "passive"))
      (node (ref "C43") (pin "2") (pinfunction "2_2") (pintype "passive"))
      (node (ref "R31") (pin "2") (pinfunction "2_2") (pintype "passive"))
    )
    (net (code "15") (name "Net-(C40-Pad1)") (class "Default")
      (node (ref "C40") (pin "1") (pinfunction "1_1") (pintype "passive"))
      (node (ref "R20") (pin "1") (pinfunction "1_1") (pintype "passive"))
      (node (ref "R23") (pin "1") (pinfunction "1_1") (pintype "passive"))
      (node (ref "R29") (pin "2") (pinfunction "2_2") (pintype "passive"))
    )
    (net (code "16") (name "Net-(C41-Pad1)") (class "Default")
      (node (ref "C41") (pin "1") (pinfunction "1_1") (pintype "passive"))
      (node (ref "R19") (pin "1") (pinfunction "1_1") (pintype "passive"))
      (node (ref "R22") (pin "2") (pinfunction "2_2") (pintype "passive"))
    )
    (net (code "17") (name "Net-(C43-Pad1)") (class "Default")
      (node (ref "C43") (pin "1") (pinfunction "1_1") (pintype "passive"))
      (node (ref "R27") (pin "2") (pinfunction "2_2") (pintype "passive"))
      (node (ref "R31") (pin "1") (pinfunction "1_1") (pintype "passive"))
    )
    (net (code "18") (name "Net-(C49-Pad1)") (class "Default")
      (node (ref "C49") (pin "1") (pinfunction "1_1") (pintype "passive"))
      (node (ref "R24") (pin "2") (pinfunction "2_2") (pintype "passive"))
      (node (ref "R25") (pin "1") (pinfunction "1_1") (pintype "passive"))
      (node (ref "R26") (pin "1") (pinfunction "1_1") (pintype "passive"))
    )
    (net (code "19") (name "Net-(C66-Pad1)") (class "Default")
      (node (ref "C66") (pin "1") (pinfunction "1_1") (pintype "passive"))
      (node (ref "R45") (pin "1") (pinfunction "1_1") (pintype "passive"))
      (node (ref "R53") (pin "1") (pinfunction "1_1") (pintype "passive"))
      (node (ref "R62") (pin "2") (pinfunction "2_2") (pintype "passive"))
    )
    (net (code "20") (name "Net-(C69-Pad1)") (class "Default")
      (node (ref "C69") (pin "1") (pinfunction "1_1") (pintype "passive"))
      (node (ref "R49") (pin "1") (pinfunction "1_1") (pintype "passive"))
      (node (ref "R52") (pin "2") (pinfunction "2_2") (pintype "passive"))
    )
    (net (code "21") (name "Net-(C71-Pad1)") (class "Default")
      (node (ref "C71") (pin "1") (pinfunction "1_1") (pintype "passive"))
      (node (ref "R58") (pin "2") (pinfunction "2_2") (pintype "passive"))
      (node (ref "R63") (pin "1") (pinfunction "1_1") (pintype "passive"))
    )
    (net (code "22") (name "Net-(C77-Pad1)") (class "Default")
      (node (ref "C77") (pin "1") (pinfunction "1_1") (pintype "passive"))
      (node (ref "R54") (pin "2") (pinfunction "2_2") (pintype "passive"))
      (node (ref "R57") (pin "1") (pinfunction "1_1") (pintype "passive"))
      (node (ref "R65") (pin "1") (pinfunction "1_1") (pintype "passive"))
    )
    (net (code "23") (name "Net-(LED1-A)") (class "Default")
      (node (ref "LED1") (pin "1") (pinfunction "A_1") (pintype "passive"))
      (node (ref "U8") (pin "38") (pinfunction "OVFR_38") (pintype "passive"))
    )
    (net (code "24") (name "Net-(LED1-K)") (class "Default")
      (node (ref "LED1") (pin "2") (pinfunction "K_2") (pintype "passive"))
      (node (ref "R43") (pin "1") (pinfunction "1_1") (pintype "passive"))
    )
    (net (code "25") (name "Net-(LED2-A)") (class "Default")
      (node (ref "LED2") (pin "1") (pinfunction "A_1") (pintype "passive"))
      (node (ref "U8") (pin "37") (pinfunction "OVFL_37") (pintype "passive"))
    )
    (net (code "26") (name "Net-(LED2-K)") (class "Default")
      (node (ref "LED2") (pin "2") (pinfunction "K_2") (pintype "passive"))
      (node (ref "R44") (pin "1") (pinfunction "1_1") (pintype "passive"))
    )
    (net (code "27") (name "Net-(OP1-+)") (class "Default")
      (node (ref "C29") (pin "2") (pinfunction "2_2") (pintype "passive"))
      (node (ref "OP1") (pin "3") (pinfunction "+_3") (pintype "passive"))
      (node (ref "R17") (pin "1") (pinfunction "1_1") (pintype "passive"))
      (node (ref "R18") (pin "1") (pinfunction "1_1") (pintype "passive"))
    )
    (net (code "28") (name "Net-(OP2-+)") (class "Default")
      (node (ref "C75") (pin "2") (pinfunction "2_2") (pintype "passive"))
      (node (ref "OP2") (pin "3") (pinfunction "+_3") (pintype "passive"))
      (node (ref "R64") (pin "1") (pinfunction "1_1") (pintype "passive"))
      (node (ref "R66") (pin "1") (pinfunction "1_1") (pintype "passive"))
    )
    (net (code "29") (name "Net-(U7-IN+)") (class "Default")
      (node (ref "C45") (pin "2") (pinfunction "2_2") (pintype "passive"))
      (node (ref "C49") (pin "2") (pinfunction "2_2") (pintype "passive"))
      (node (ref "R25") (pin "2") (pinfunction "2_2") (pintype "passive"))
      (node (ref "R27") (pin "1") (pinfunction "1_1") (pintype "passive"))
      (node (ref "U7") (pin "8") (pinfunction "IN+_8") (pintype "passive"))
    )
    (net (code "30") (name "Net-(U7-IN-)") (class "Default")
      (node (ref "C38") (pin "2") (pinfunction "2_2") (pintype "passive"))
      (node (ref "C40") (pin "2") (pinfunction "2_2") (pintype "passive"))
      (node (ref "R20") (pin "2") (pinfunction "2_2") (pintype "passive"))
      (node (ref "R22") (pin "1") (pinfunction "1_1") (pintype "passive"))
      (node (ref "U7") (pin "1") (pinfunction "IN-_1") (pintype "passive"))
    )
    (net (code "31") (name "Net-(U7-O-)") (class "Default")
      (node (ref "C45") (pin "1") (pinfunction "1_1") (pintype "passive"))
      (node (ref "R26") (pin "2") (pinfunction "2_2") (pintype "passive"))
      (node (ref "U7") (pin "5") (pinfunction "O-_5") (pintype "passive"))
    )
    (net (code "32") (name "Net-(U7-OUT+)") (class "Default")
      (node (ref "C38") (pin "1") (pinfunction "1_1") (pintype "passive"))
      (node (ref "R23") (pin "2") (pinfunction "2_2") (pintype "passive"))
      (node (ref "U7") (pin "4") (pinfunction "OUT+_4") (pintype "passive"))
    )
    (net (code "33") (name "Net-(U8-BCK)") (class "Default")
      (node (ref "R13") (pin "2") (pinfunction "2_2") (pintype "passive"))
      (node (ref "U8") (pin "33") (pinfunction "BCK_33") (pintype "passive"))
    )
    (net (code "34") (name "Net-(U8-DATA)") (class "Default")
      (node (ref "R13") (pin "3") (pinfunction "3_3") (pintype "passive"))
      (node (ref "U8") (pin "32") (pinfunction "DATA_32") (pintype "passive"))
    )
    (net (code "35") (name "Net-(U8-DF{slash}MOD5)") (class "Default")
      (node (ref "R46") (pin "2") (pinfunction "2_2") (pintype "passive"))
      (node (ref "R59") (pin "2") (pinfunction "2_2") (pintype "passive"))
      (node (ref "U8") (pin "21") (pinfunction "DF/MOD5_21") (pintype "passive"))
    )
    (net (code "36") (name "Net-(U8-DSDEN{slash}MOD6)") (class "Default")
      (node (ref "R33") (pin "2") (pinfunction "2_2") (pintype "passive"))
      (node (ref "U8") (pin "22") (pinfunction "DSDEN/MOD6_22") (pintype "passive"))
    )
    (net (code "37") (name "Net-(U8-DSDMODE)") (class "Default")
      (node (ref "R32") (pin "2") (pinfunction "2_2") (pintype "passive"))
      (node (ref "U8") (pin "24") (pinfunction "DSDMODE_24") (pintype "passive"))
    )
    (net (code "38") (name "Net-(U8-FMT0)") (class "Default")
      (node (ref "R39") (pin "1") (pinfunction "1_1") (pintype "passive"))
      (node (ref "R40") (pin "1") (pinfunction "1_1") (pintype "passive"))
      (node (ref "U8") (pin "44") (pinfunction "FMT0_44") (pintype "passive"))
    )
    (net (code "39") (name "Net-(U8-FMT1)") (class "Default")
      (node (ref "R38") (pin "1") (pinfunction "1_1") (pintype "passive"))
      (node (ref "U8") (pin "43") (pinfunction "FMT1_43") (pintype "passive"))
    )
    (net (code "40") (name "Net-(U8-FS0{slash}MOD3)") (class "Default")
      (node (ref "R48") (pin "1") (pinfunction "1_1") (pintype "passive"))
      (node (ref "R60") (pin "2") (pinfunction "2_2") (pintype "passive"))
      (node (ref "U8") (pin "19") (pinfunction "FS0/MOD3_19") (pintype "passive"))
    )
    (net (code "41") (name "Net-(U8-FS1{slash}MOD4)") (class "Default")
      (node (ref "R47") (pin "1") (pinfunction "1_1") (pintype "passive"))
      (node (ref "R55") (pin "2") (pinfunction "2_2") (pintype "passive"))
      (node (ref "U8") (pin "20") (pinfunction "FS1/MOD4_20") (pintype "passive"))
    )
    (net (code "42") (name "Net-(U8-HPFDL{slash}MOD2)") (class "Default")
      (node (ref "R50") (pin "1") (pinfunction "1_1") (pintype "passive"))
      (node (ref "R56") (pin "2") (pinfunction "2_2") (pintype "passive"))
      (node (ref "U8") (pin "18") (pinfunction "HPFDL/MOD2_18") (pintype "passive"))
    )
    (net (code "43") (name "Net-(U8-HPFDR{slash}MOD1)") (class "Default")
      (node (ref "R51") (pin "2") (pinfunction "2_2") (pintype "passive"))
      (node (ref "R61") (pin "2") (pinfunction "2_2") (pintype "passive"))
      (node (ref "U8") (pin "17") (pinfunction "HPFDR/MOD1_17") (pintype "passive"))
    )
    (net (code "44") (name "Net-(U8-LRCK)") (class "Default")
      (node (ref "R13") (pin "1") (pinfunction "1_1") (pintype "passive"))
      (node (ref "U8") (pin "34") (pinfunction "LRCK_34") (pintype "passive"))
    )
    (net (code "45") (name "Net-(U8-MCKI)") (class "Default")
      (node (ref "R41") (pin "1") (pinfunction "1_1") (pintype "passive"))
      (node (ref "U8") (pin "35") (pinfunction "MCKI_35") (pintype "passive"))
    )
    (net (code "46") (name "Net-(U8-MODEN)") (class "Default")
      (node (ref "R30") (pin "2") (pinfunction "2_2") (pintype "passive"))
      (node (ref "U8") (pin "23") (pinfunction "MODEN_23") (pintype "passive"))
    )
    (net (code "47") (name "Net-(U8-OWL0)") (class "Default")
      (node (ref "R36") (pin "1") (pinfunction "1_1") (pintype "passive"))
      (node (ref "U8") (pin "42") (pinfunction "OWL0_42") (pintype "passive"))
    )
    (net (code "48") (name "Net-(U8-OWL1)") (class "Default")
      (node (ref "R35") (pin "1") (pinfunction "1_1") (pintype "passive"))
      (node (ref "U8") (pin "41") (pinfunction "OWL1_41") (pintype "passive"))
    )
    (net (code "49") (name "Net-(U8-PCMEN)") (class "Default")
      (node (ref "R28") (pin "2") (pinfunction "2_2") (pintype "passive"))
      (node (ref "U8") (pin "16") (pinfunction "PCMEN_16") (pintype "passive"))
    )
    (net (code "50") (name "Net-(U8-RST-)") (class "Default")
      (node (ref "R42") (pin "1") (pinfunction "1_1") (pintype "passive"))
      (node (ref "U8") (pin "36") (pinfunction "RST-_36") (pintype "passive"))
    )
    (net (code "51") (name "Net-(U8-S{slash}M-)") (class "Default")
      (node (ref "R34") (pin "1") (pinfunction "1_1") (pintype "passive"))
      (node (ref "U8") (pin "39") (pinfunction "S/M-_39") (pintype "passive"))
    )
    (net (code "52") (name "Net-(U8-VINL+)") (class "Default")
      (node (ref "C70") (pin "2") (pinfunction "2_2") (pintype "passive"))
      (node (ref "R62") (pin "1") (pinfunction "1_1") (pintype "passive"))
      (node (ref "U8") (pin "11") (pinfunction "VINL+_11") (pintype "passive"))
    )
    (net (code "53") (name "Net-(U8-VINL-)") (class "Default")
      (node (ref "C70") (pin "1") (pinfunction "1_1") (pintype "passive"))
      (node (ref "R54") (pin "1") (pinfunction "1_1") (pintype "passive"))
      (node (ref "U8") (pin "10") (pinfunction "VINL-_10") (pintype "passive"))
    )
    (net (code "54") (name "Net-(U8-VINR+)") (class "Default")
      (node (ref "C42") (pin "2") (pinfunction "2_2") (pintype "passive"))
      (node (ref "R29") (pin "1") (pinfunction "1_1") (pintype "passive"))
      (node (ref "U8") (pin "3") (pinfunction "VINR+_3") (pintype "passive"))
    )
    (net (code "55") (name "Net-(U8-VINR-)") (class "Default")
      (node (ref "C42") (pin "1") (pinfunction "1_1") (pintype "passive"))
      (node (ref "R24") (pin "1") (pinfunction "1_1") (pintype "passive"))
      (node (ref "U8") (pin "2") (pinfunction "VINR-_2") (pintype "passive"))
    )
    (net (code "56") (name "Net-(U8-VREFL)") (class "Default")
      (node (ref "C61") (pin "1") (pinfunction "1_1") (pintype "passive"))
      (node (ref "C62") (pin "2") (pinfunction "2_2") (pintype "passive"))
      (node (ref "U8") (pin "15") (pinfunction "VREFL_15") (pintype "passive"))
    )
    (net (code "57") (name "Net-(U8-VREFR)") (class "Default")
      (node (ref "C47") (pin "1") (pinfunction "1_1") (pintype "passive"))
      (node (ref "C48") (pin "2") (pinfunction "2_2") (pintype "passive"))
      (node (ref "U8") (pin "46") (pinfunction "VREFR_46") (pintype "passive"))
    )
    (net (code "58") (name "Net-(U9-IN+)") (class "Default")
      (node (ref "C74") (pin "2") (pinfunction "2_2") (pintype "passive"))
      (node (ref "C77") (pin "2") (pinfunction "2_2") (pintype "passive"))
      (node (ref "R58") (pin "1") (pinfunction "1_1") (pintype "passive"))
      (node (ref "R65") (pin "2") (pinfunction "2_2") (pintype "passive"))
      (node (ref "U9") (pin "8") (pinfunction "IN+_8") (pintype "passive"))
    )
    (net (code "59") (name "Net-(U9-IN-)") (class "Default")
      (node (ref "C66") (pin "2") (pinfunction "2_2") (pintype "passive"))
      (node (ref "C67") (pin "2") (pinfunction "2_2") (pintype "passive"))
      (node (ref "R45") (pin "2") (pinfunction "2_2") (pintype "passive"))
      (node (ref "R52") (pin "1") (pinfunction "1_1") (pintype "passive"))
      (node (ref "U9") (pin "1") (pinfunction "IN-_1") (pintype "passive"))
    )
    (net (code "60") (name "Net-(U9-O-)") (class "Default")
      (node (ref "C74") (pin "1") (pinfunction "1_1") (pintype "passive"))
      (node (ref "R57") (pin "2") (pinfunction "2_2") (pintype "passive"))
      (node (ref "U9") (pin "5") (pinfunction "O-_5") (pintype "passive"))
    )
    (net (code "61") (name "Net-(U9-OUT+)") (class "Default")
      (node (ref "C67") (pin "1") (pinfunction "1_1") (pintype "passive"))
      (node (ref "R53") (pin "2") (pinfunction "2_2") (pintype "passive"))
      (node (ref "U9") (pin "4") (pinfunction "OUT+_4") (pintype "passive"))
    )
    (net (code "62") (name "Net-(Y1-OUT)") (class "Default")
      (node (ref "R41") (pin "2") (pinfunction "2_2") (pintype "passive"))
      (node (ref "Y1") (pin "3") (pinfunction "OUT_3") (pintype "passive"))
      (node (ref "Y2") (pin "3") (pinfunction "OUT_3") (pintype "passive"))
    )
    (net (code "63") (name "VCML") (class "Default")
      (node (ref "OP2") (pin "2") (pinfunction "-_2") (pintype "passive"))
      (node (ref "OP2") (pin "6") (pinfunction "O_6") (pintype "passive"))
      (node (ref "R66") (pin "2") (pinfunction "2_2") (pintype "passive"))
      (node (ref "U9") (pin "2") (pinfunction "VOCM_2") (pintype "passive"))
    )
    (net (code "64") (name "VCMR") (class "Default")
      (node (ref "OP1") (pin "2") (pinfunction "-_2") (pintype "passive"))
      (node (ref "OP1") (pin "6") (pinfunction "O_6") (pintype "passive"))
      (node (ref "R18") (pin "2") (pinfunction "2_2") (pintype "passive"))
      (node (ref "U7") (pin "2") (pinfunction "VOCM_2") (pintype "passive"))
    )
    (net (code "65") (name "unconnected-(R13-Pad4)") (class "Default")
      (node (ref "R13") (pin "4") (pinfunction "4_4") (pintype "passive"))
    )
    (net (code "66") (name "unconnected-(R13-Pad5)") (class "Default")
      (node (ref "R13") (pin "5") (pinfunction "5_5") (pintype "passive"))
    )
    (net (code "67") (name "unconnected-(U7-EN-Pad7)") (class "Default")
      (node (ref "U7") (pin "7") (pinfunction "EN_7") (pintype "passive"))
    )
    (net (code "68") (name "unconnected-(U8-AGND-Pad5)") (class "Default")
      (node (ref "U8") (pin "5") (pinfunction "AGND_5") (pintype "passive"))
    )
    (net (code "69") (name "unconnected-(U8-AGND-Pad6)") (class "Default")
      (node (ref "U8") (pin "6") (pinfunction "AGND_6") (pintype "passive"))
    )
    (net (code "70") (name "unconnected-(U8-AGND-Pad8)") (class "Default")
      (node (ref "U8") (pin "8") (pinfunction "AGND_8") (pintype "passive"))
    )
    (net (code "71") (name "unconnected-(U8-DSDCLK-Pad27)") (class "Default")
      (node (ref "U8") (pin "27") (pinfunction "DSDCLK_27") (pintype "passive"))
    )
    (net (code "72") (name "unconnected-(U8-DSDL-Pad28)") (class "Default")
      (node (ref "U8") (pin "28") (pinfunction "DSDL_28") (pintype "passive"))
    )
    (net (code "73") (name "unconnected-(U8-DSDR-Pad29)") (class "Default")
      (node (ref "U8") (pin "29") (pinfunction "DSDR_29") (pintype "passive"))
    )
    (net (code "74") (name "unconnected-(U8-SUB0{slash}WCKO-Pad26)") (class "Default")
      (node (ref "U8") (pin "26") (pinfunction "SUB0/WCKO_26") (pintype "passive+no_connect"))
    )
    (net (code "75") (name "unconnected-(U8-SUB1{slash}MCKO-Pad25)") (class "Default")
      (node (ref "U8") (pin "25") (pinfunction "SUB1/MCKO_25") (pintype "passive+no_connect"))
    )
    (net (code "76") (name "unconnected-(U9-EN-Pad7)") (class "Default")
      (node (ref "U9") (pin "7") (pinfunction "EN_7") (pintype "passive"))
    )
    (net (code "77") (name "unconnected-(Y1-AFC{slash}GND-Pad1)") (class "Default")
      (node (ref "Y1") (pin "1") (pinfunction "AFC/GND_1") (pintype "passive"))
    )
    (net (code "78") (name "unconnected-(Y2-AFC{slash}GND-Pad1)") (class "Default")
      (node (ref "Y2") (pin "1") (pinfunction "AFC/GND_1") (pintype "passive"))
    )
  )
)
